# OneDigitDisplay.net
KiCad netlist of a schematic drawn in EAGLE
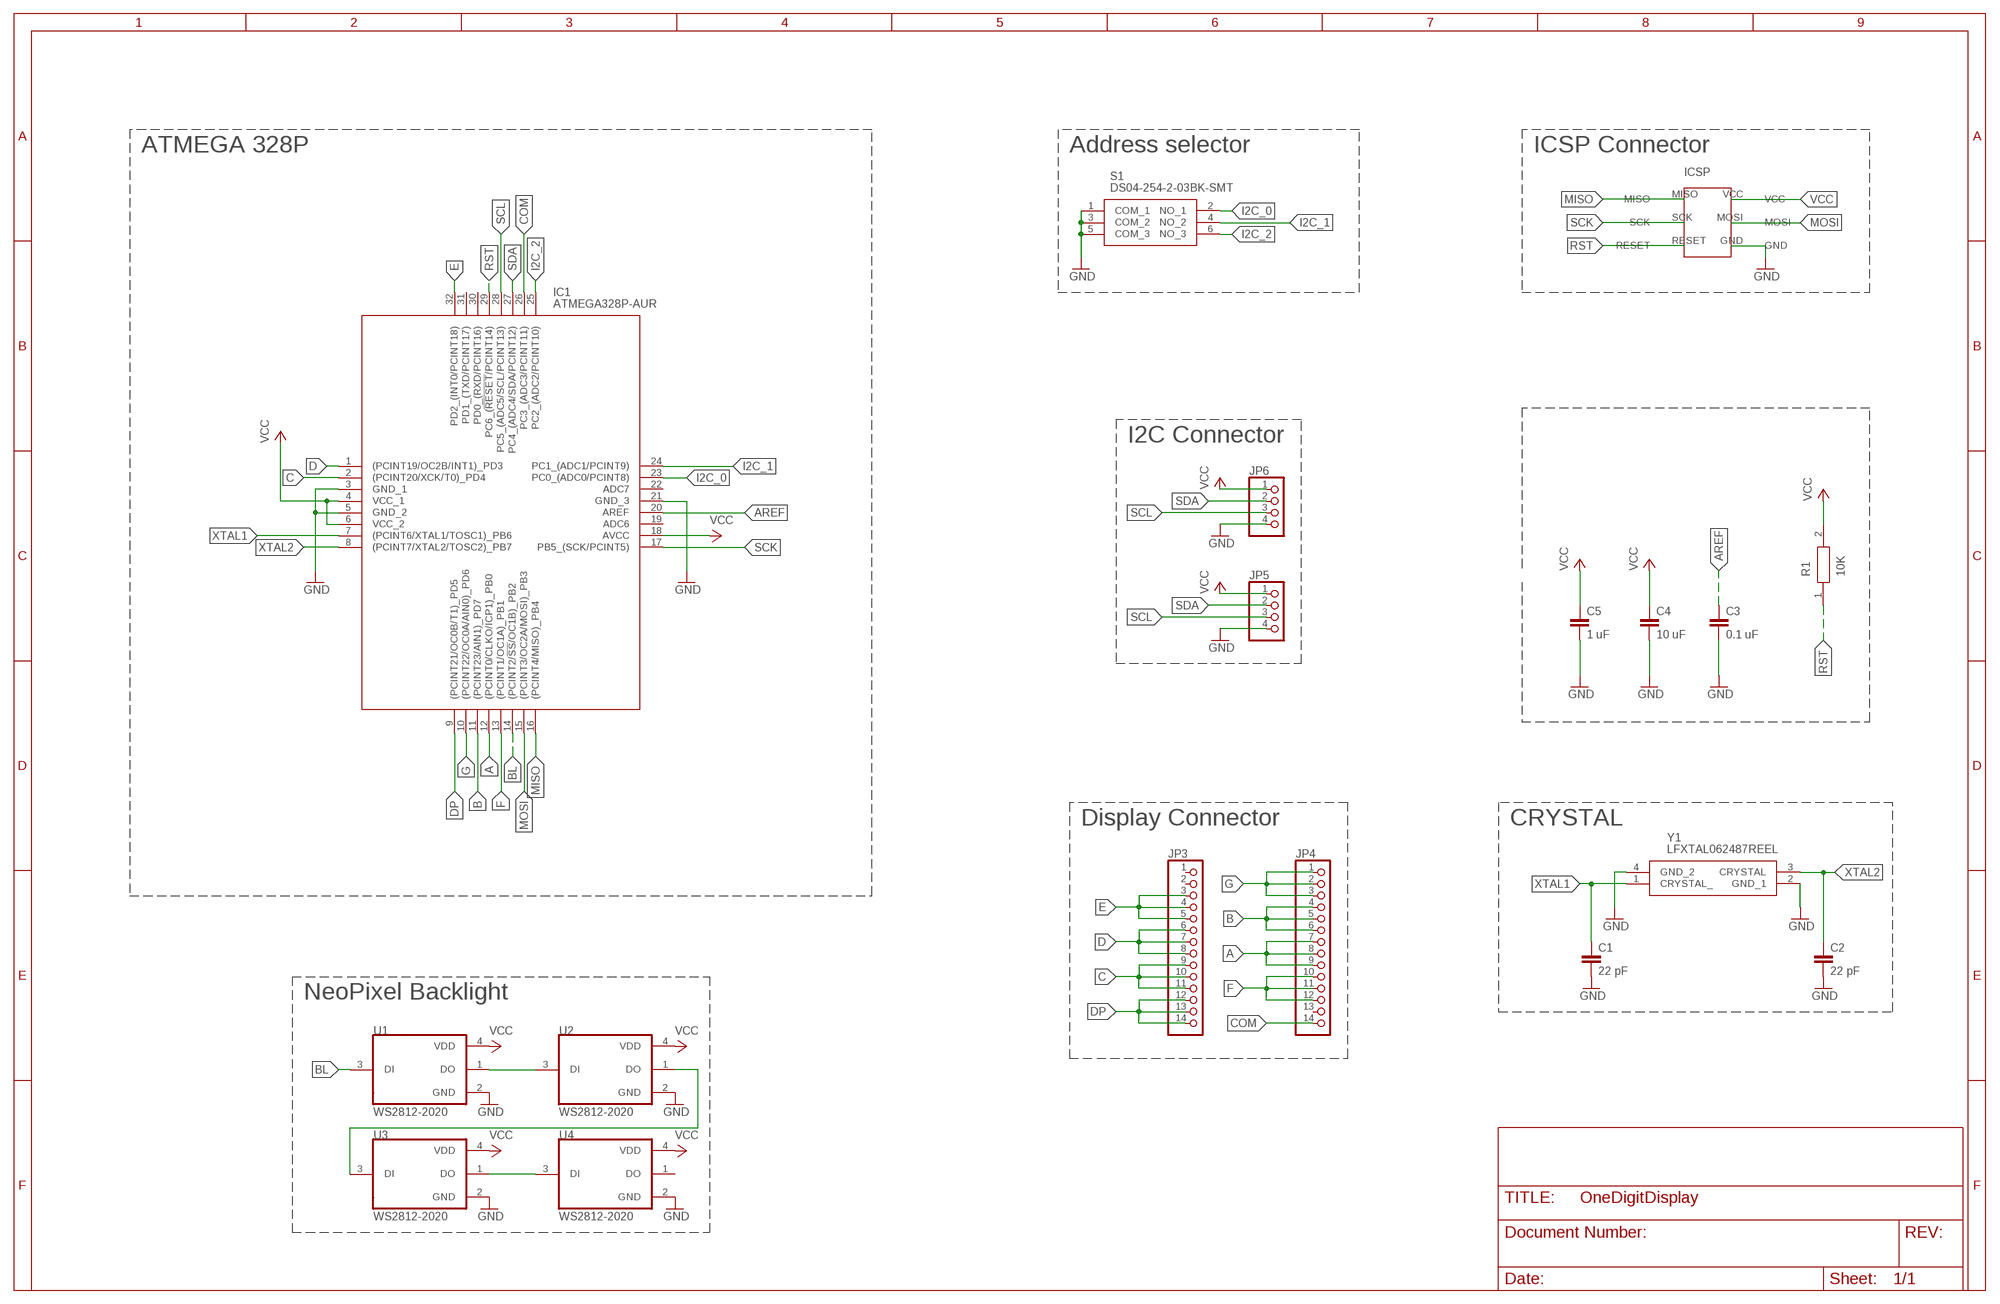
[diagram p0: schematic, sheet 1]

(export (version "E")
  (design (tool "Eeschema 10.0.6"))
  (components
    (comp (ref "C1")
      (value "22 pF")
      (footprint "eagle-import:C0603K")
      (libsource (lib "eagle-import") (part "C-EUC0603K"))
    )
    (comp (ref "C2")
      (value "22 pF")
      (footprint "eagle-import:C0603K")
      (libsource (lib "eagle-import") (part "C-EUC0603K"))
    )
    (comp (ref "C3")
      (value "0.1 uF")
      (footprint "eagle-import:C0603")
      (libsource (lib "eagle-import") (part "C-EUC0603"))
    )
    (comp (ref "C4")
      (value "10 uF")
      (footprint "eagle-import:C0603")
      (libsource (lib "eagle-import") (part "C-EUC0603"))
    )
    (comp (ref "C5")
      (value "1 uF")
      (footprint "eagle-import:C0603")
      (libsource (lib "eagle-import") (part "C-EUC0603"))
    )
    (comp (ref "IC1")
      (value "ATMEGA328P-AUR")
      (footprint "eagle-import:QFP80P900X900X120-32N")
      (fields (field (name "MOUSER_PART_NUMBER") "556-ATMEGA328P-AUR"))
      (libsource (lib "eagle-import") (part "ATMEGA328P-AUR"))
    )
    (comp (ref "JP3")
      (value "PINHD-1X14")
      (footprint "eagle-import:1X14")
      (fields (field (name "SPICEPREFIX") "X"))
      (libsource (lib "eagle-import") (part "PINHD-1X14"))
    )
    (comp (ref "JP4")
      (value "PINHD-1X14")
      (footprint "eagle-import:1X14")
      (fields (field (name "SPICEPREFIX") "X"))
      (libsource (lib "eagle-import") (part "PINHD-1X14"))
    )
    (comp (ref "JP5")
      (value "PINHD-1X4")
      (footprint "eagle-import:1X04")
      (libsource (lib "eagle-import") (part "PINHD-1X4"))
    )
    (comp (ref "JP6")
      (value "PINHD-1X4")
      (footprint "eagle-import:1X04")
      (libsource (lib "eagle-import") (part "PINHD-1X4"))
    )
    (comp (ref "R1")
      (value "10K")
      (footprint "eagle-import:RESC1608X55N")
      (fields
        (field (name "MANUFACTURER_PART_NUMBER") "TNPW060330K0BXEA")
        (field (name "MOUSER_PART_NUMBER") "71-TNPW060330K0BXEA")
      )
      (libsource (lib "eagle-import") (part "TNPW060330K0BXEA"))
    )
    (comp (ref "S1")
      (value "DS04-254-2-03BK-SMT")
      (footprint "eagle-import:DS04254203BKSMT")
      (fields (field (name "MOUSER_PART_NUMBER") "490-DS04254203BK-SMT"))
      (libsource (lib "eagle-import") (part "DS04-254-2-03BK-SMT"))
    )
    (comp (ref "U$1")
      (value "6PINICSP")
      (footprint "eagle-import:6PINICSP")
      (libsource (lib "eagle-import") (part "6PINICSP"))
    )
    (comp (ref "U1")
      (value "WS2812-2020")
      (footprint "eagle-import:LED_WS2812-2020")
      (fields (field (name "MF") "Worldsemi"))
      (libsource (lib "eagle-import") (part "WS2812-2020"))
    )
    (comp (ref "U2")
      (value "WS2812-2020")
      (footprint "eagle-import:LED_WS2812-2020")
      (fields (field (name "MF") "Worldsemi"))
      (libsource (lib "eagle-import") (part "WS2812-2020"))
    )
    (comp (ref "U3")
      (value "WS2812-2020")
      (footprint "eagle-import:LED_WS2812-2020")
      (fields (field (name "MF") "Worldsemi"))
      (libsource (lib "eagle-import") (part "WS2812-2020"))
    )
    (comp (ref "U4")
      (value "WS2812-2020")
      (footprint "eagle-import:LED_WS2812-2020")
      (fields (field (name "MF") "Worldsemi"))
      (libsource (lib "eagle-import") (part "WS2812-2020"))
    )
    (comp (ref "Y1")
      (value "LFXTAL062487REEL")
      (footprint "eagle-import:LFXTAL062487REEL")
      (fields
        (field (name "MANUFACTURER_PART_NUMBER") "LFXTAL062487Reel")
        (field (name "MOUSER_PART_NUMBER") "449-LFXTAL062487REEL")
      )
      (libsource (lib "eagle-import") (part "LFXTAL062487REEL"))
    )
  )
  (nets
    (net (code "1") (name "A") (class "Default")
      (node (ref "IC1") (pin "12") (pinfunction "(PCINT0/CLKO/ICP1)_PB0_12") (pintype "bidirectional"))
      (node (ref "JP4") (pin "7") (pinfunction "7_7") (pintype "passive"))
      (node (ref "JP4") (pin "8") (pinfunction "8_8") (pintype "passive"))
      (node (ref "JP4") (pin "9") (pinfunction "9_9") (pintype "passive"))
    )
    (net (code "2") (name "AREF") (class "Default")
      (node (ref "C3") (pin "1") (pinfunction "1_1") (pintype "passive"))
      (node (ref "IC1") (pin "20") (pinfunction "AREF_20") (pintype "bidirectional"))
    )
    (net (code "3") (name "B") (class "Default")
      (node (ref "IC1") (pin "11") (pinfunction "(PCINT23/AIN1)_PD7_11") (pintype "bidirectional"))
      (node (ref "JP4") (pin "4") (pinfunction "4_4") (pintype "passive"))
      (node (ref "JP4") (pin "5") (pinfunction "5_5") (pintype "passive"))
      (node (ref "JP4") (pin "6") (pinfunction "6_6") (pintype "passive"))
    )
    (net (code "4") (name "BL") (class "Default")
      (node (ref "IC1") (pin "14") (pinfunction "(PCINT2/~{SS}/OC1B)_PB2_14") (pintype "bidirectional"))
      (node (ref "U1") (pin "3") (pinfunction "DI_3") (pintype "input"))
    )
    (net (code "5") (name "C") (class "Default")
      (node (ref "IC1") (pin "2") (pinfunction "(PCINT20/XCK/T0)_PD4_2") (pintype "bidirectional"))
      (node (ref "JP3") (pin "10") (pinfunction "10_10") (pintype "passive"))
      (node (ref "JP3") (pin "11") (pinfunction "11_11") (pintype "passive"))
      (node (ref "JP3") (pin "9") (pinfunction "9_9") (pintype "passive"))
    )
    (net (code "6") (name "COM") (class "Default")
      (node (ref "IC1") (pin "26") (pinfunction "PC3_(ADC3/PCINT11)_26") (pintype "bidirectional"))
      (node (ref "JP4") (pin "14") (pinfunction "14_14") (pintype "passive"))
    )
    (net (code "7") (name "D") (class "Default")
      (node (ref "IC1") (pin "1") (pinfunction "(PCINT19/OC2B/INT1)_PD3_1") (pintype "bidirectional"))
      (node (ref "JP3") (pin "6") (pinfunction "6_6") (pintype "passive"))
      (node (ref "JP3") (pin "7") (pinfunction "7_7") (pintype "passive"))
      (node (ref "JP3") (pin "8") (pinfunction "8_8") (pintype "passive"))
    )
    (net (code "8") (name "DP") (class "Default")
      (node (ref "IC1") (pin "9") (pinfunction "(PCINT21/OC0B/T1)_PD5_9") (pintype "bidirectional"))
      (node (ref "JP3") (pin "12") (pinfunction "12_12") (pintype "passive"))
      (node (ref "JP3") (pin "13") (pinfunction "13_13") (pintype "passive"))
      (node (ref "JP3") (pin "14") (pinfunction "14_14") (pintype "passive"))
    )
    (net (code "9") (name "E") (class "Default")
      (node (ref "IC1") (pin "32") (pinfunction "PD2_(INT0/PCINT18)_32") (pintype "bidirectional"))
      (node (ref "JP3") (pin "3") (pinfunction "3_3") (pintype "passive"))
      (node (ref "JP3") (pin "4") (pinfunction "4_4") (pintype "passive"))
      (node (ref "JP3") (pin "5") (pinfunction "5_5") (pintype "passive"))
    )
    (net (code "10") (name "F") (class "Default")
      (node (ref "IC1") (pin "13") (pinfunction "(PCINT1/OC1A)_PB1_13") (pintype "bidirectional"))
      (node (ref "JP4") (pin "10") (pinfunction "10_10") (pintype "passive"))
      (node (ref "JP4") (pin "11") (pinfunction "11_11") (pintype "passive"))
      (node (ref "JP4") (pin "12") (pinfunction "12_12") (pintype "passive"))
    )
    (net (code "11") (name "G") (class "Default")
      (node (ref "IC1") (pin "10") (pinfunction "(PCINT22/OC0A/AIN0)_PD6_10") (pintype "bidirectional"))
      (node (ref "JP4") (pin "1") (pinfunction "1_1") (pintype "passive"))
      (node (ref "JP4") (pin "2") (pinfunction "2_2") (pintype "passive"))
      (node (ref "JP4") (pin "3") (pinfunction "3_3") (pintype "passive"))
    )
    (net (code "12") (name "GND") (class "Default")
      (node (ref "C1") (pin "2") (pinfunction "2_2") (pintype "passive"))
      (node (ref "C2") (pin "2") (pinfunction "2_2") (pintype "passive"))
      (node (ref "C3") (pin "2") (pinfunction "2_2") (pintype "passive"))
      (node (ref "C4") (pin "2") (pinfunction "2_2") (pintype "passive"))
      (node (ref "C5") (pin "2") (pinfunction "2_2") (pintype "passive"))
      (node (ref "IC1") (pin "21") (pinfunction "GND_3_21") (pintype "bidirectional"))
      (node (ref "IC1") (pin "3") (pinfunction "GND_1_3") (pintype "bidirectional"))
      (node (ref "IC1") (pin "5") (pinfunction "GND_2_5") (pintype "bidirectional"))
      (node (ref "JP5") (pin "4") (pinfunction "4_4") (pintype "passive"))
      (node (ref "JP6") (pin "4") (pinfunction "4_4") (pintype "passive"))
      (node (ref "S1") (pin "1") (pinfunction "COM_1_1") (pintype "bidirectional"))
      (node (ref "S1") (pin "3") (pinfunction "COM_2_3") (pintype "bidirectional"))
      (node (ref "S1") (pin "5") (pinfunction "COM_3_5") (pintype "bidirectional"))
      (node (ref "U$1") (pin "GND") (pinfunction "GND_GND") (pintype "bidirectional"))
      (node (ref "U1") (pin "2") (pinfunction "GND_2") (pintype "power_in"))
      (node (ref "U2") (pin "2") (pinfunction "GND_2") (pintype "power_in"))
      (node (ref "U3") (pin "2") (pinfunction "GND_2") (pintype "power_in"))
      (node (ref "U4") (pin "2") (pinfunction "GND_2") (pintype "power_in"))
      (node (ref "Y1") (pin "2") (pinfunction "GND_1_2") (pintype "bidirectional"))
      (node (ref "Y1") (pin "4") (pinfunction "GND_2_4") (pintype "bidirectional"))
    )
    (net (code "13") (name "I2C_0") (class "Default")
      (node (ref "IC1") (pin "23") (pinfunction "PC0_(ADC0/PCINT8)_23") (pintype "bidirectional"))
      (node (ref "S1") (pin "2") (pinfunction "NO_1_2") (pintype "bidirectional"))
    )
    (net (code "14") (name "I2C_1") (class "Default")
      (node (ref "IC1") (pin "24") (pinfunction "PC1_(ADC1/PCINT9)_24") (pintype "bidirectional"))
      (node (ref "S1") (pin "4") (pinfunction "NO_2_4") (pintype "bidirectional"))
    )
    (net (code "15") (name "I2C_2") (class "Default")
      (node (ref "IC1") (pin "25") (pinfunction "PC2_(ADC2/PCINT10)_25") (pintype "bidirectional"))
      (node (ref "S1") (pin "6") (pinfunction "NO_3_6") (pintype "bidirectional"))
    )
    (net (code "16") (name "MISO") (class "Default")
      (node (ref "IC1") (pin "16") (pinfunction "(PCINT4/MISO)_PB4_16") (pintype "bidirectional"))
      (node (ref "U$1") (pin "MISO") (pinfunction "MISO_MISO") (pintype "bidirectional"))
    )
    (net (code "17") (name "MOSI") (class "Default")
      (node (ref "IC1") (pin "15") (pinfunction "(PCINT3/OC2A/MOSI)_PB3_15") (pintype "bidirectional"))
      (node (ref "U$1") (pin "MOSI") (pinfunction "MOSI_MOSI") (pintype "bidirectional"))
    )
    (net (code "18") (name "Net-(U1-DO)") (class "Default")
      (node (ref "U1") (pin "1") (pinfunction "DO_1") (pintype "output"))
      (node (ref "U2") (pin "3") (pinfunction "DI_3") (pintype "input"))
    )
    (net (code "19") (name "Net-(U2-DO)") (class "Default")
      (node (ref "U2") (pin "1") (pinfunction "DO_1") (pintype "output"))
      (node (ref "U3") (pin "3") (pinfunction "DI_3") (pintype "input"))
    )
    (net (code "20") (name "Net-(U3-DO)") (class "Default")
      (node (ref "U3") (pin "1") (pinfunction "DO_1") (pintype "output"))
      (node (ref "U4") (pin "3") (pinfunction "DI_3") (pintype "input"))
    )
    (net (code "21") (name "RST") (class "Default")
      (node (ref "IC1") (pin "29") (pinfunction "PC6_(~{RESET}/PCINT14)_29") (pintype "bidirectional"))
      (node (ref "R1") (pin "1") (pinfunction "1_1") (pintype "bidirectional"))
      (node (ref "U$1") (pin "RESET") (pinfunction "RESET_RESET") (pintype "bidirectional"))
    )
    (net (code "22") (name "SCK") (class "Default")
      (node (ref "IC1") (pin "17") (pinfunction "PB5_(SCK/PCINT5)_17") (pintype "bidirectional"))
      (node (ref "U$1") (pin "SCK") (pinfunction "SCK_SCK") (pintype "bidirectional"))
    )
    (net (code "23") (name "SCL") (class "Default")
      (node (ref "IC1") (pin "28") (pinfunction "PC5_(ADC5/SCL/PCINT13)_28") (pintype "bidirectional"))
      (node (ref "JP5") (pin "3") (pinfunction "3_3") (pintype "passive"))
      (node (ref "JP6") (pin "3") (pinfunction "3_3") (pintype "passive"))
    )
    (net (code "24") (name "SDA") (class "Default")
      (node (ref "IC1") (pin "27") (pinfunction "PC4_(ADC4/SDA/PCINT12)_27") (pintype "bidirectional"))
      (node (ref "JP5") (pin "2") (pinfunction "2_2") (pintype "passive"))
      (node (ref "JP6") (pin "2") (pinfunction "2_2") (pintype "passive"))
    )
    (net (code "25") (name "VCC") (class "Default")
      (node (ref "C4") (pin "1") (pinfunction "1_1") (pintype "passive"))
      (node (ref "C5") (pin "1") (pinfunction "1_1") (pintype "passive"))
      (node (ref "IC1") (pin "18") (pinfunction "AVCC_18") (pintype "bidirectional"))
      (node (ref "IC1") (pin "4") (pinfunction "VCC_1_4") (pintype "bidirectional"))
      (node (ref "IC1") (pin "6") (pinfunction "VCC_2_6") (pintype "bidirectional"))
      (node (ref "JP5") (pin "1") (pinfunction "1_1") (pintype "passive"))
      (node (ref "JP6") (pin "1") (pinfunction "1_1") (pintype "passive"))
      (node (ref "R1") (pin "2") (pinfunction "2_2") (pintype "bidirectional"))
      (node (ref "U$1") (pin "VCC") (pinfunction "VCC_VCC") (pintype "bidirectional"))
      (node (ref "U1") (pin "4") (pinfunction "VDD_4") (pintype "power_in"))
      (node (ref "U2") (pin "4") (pinfunction "VDD_4") (pintype "power_in"))
      (node (ref "U3") (pin "4") (pinfunction "VDD_4") (pintype "power_in"))
      (node (ref "U4") (pin "4") (pinfunction "VDD_4") (pintype "power_in"))
    )
    (net (code "26") (name "XTAL1") (class "Default")
      (node (ref "C1") (pin "1") (pinfunction "1_1") (pintype "passive"))
      (node (ref "IC1") (pin "7") (pinfunction "(PCINT6/XTAL1/TOSC1)_PB6_7") (pintype "bidirectional"))
      (node (ref "Y1") (pin "1") (pinfunction "CRYSTAL__1") (pintype "bidirectional"))
    )
    (net (code "27") (name "XTAL2") (class "Default")
      (node (ref "C2") (pin "1") (pinfunction "1_1") (pintype "passive"))
      (node (ref "IC1") (pin "8") (pinfunction "(PCINT7/XTAL2/TOSC2)_PB7_8") (pintype "bidirectional"))
      (node (ref "Y1") (pin "3") (pinfunction "CRYSTAL_3") (pintype "bidirectional"))
    )
    (net (code "28") (name "unconnected-(IC1-ADC6-Pad19)") (class "Default")
      (node (ref "IC1") (pin "19") (pinfunction "ADC6_19") (pintype "bidirectional"))
    )
    (net (code "29") (name "unconnected-(IC1-ADC7-Pad22)") (class "Default")
      (node (ref "IC1") (pin "22") (pinfunction "ADC7_22") (pintype "bidirectional"))
    )
    (net (code "30") (name "unconnected-(IC1-PD0_(RXD{slash}PCINT16)-Pad30)") (class "Default")
      (node (ref "IC1") (pin "30") (pinfunction "PD0_(RXD/PCINT16)_30") (pintype "bidirectional"))
    )
    (net (code "31") (name "unconnected-(IC1-PD1_(TXD{slash}PCINT17)-Pad31)") (class "Default")
      (node (ref "IC1") (pin "31") (pinfunction "PD1_(TXD/PCINT17)_31") (pintype "bidirectional"))
    )
    (net (code "32") (name "unconnected-(JP3-Pad1)") (class "Default")
      (node (ref "JP3") (pin "1") (pinfunction "1_1") (pintype "passive"))
    )
    (net (code "33") (name "unconnected-(JP3-Pad2)") (class "Default")
      (node (ref "JP3") (pin "2") (pinfunction "2_2") (pintype "passive"))
    )
    (net (code "34") (name "unconnected-(JP4-Pad13)") (class "Default")
      (node (ref "JP4") (pin "13") (pinfunction "13_13") (pintype "passive"))
    )
    (net (code "35") (name "unconnected-(U4-DO-Pad1)") (class "Default")
      (node (ref "U4") (pin "1") (pinfunction "DO_1") (pintype "output"))
    )
  )
)
